# G778A.net
KiCad netlist of a schematic drawn in EAGLE
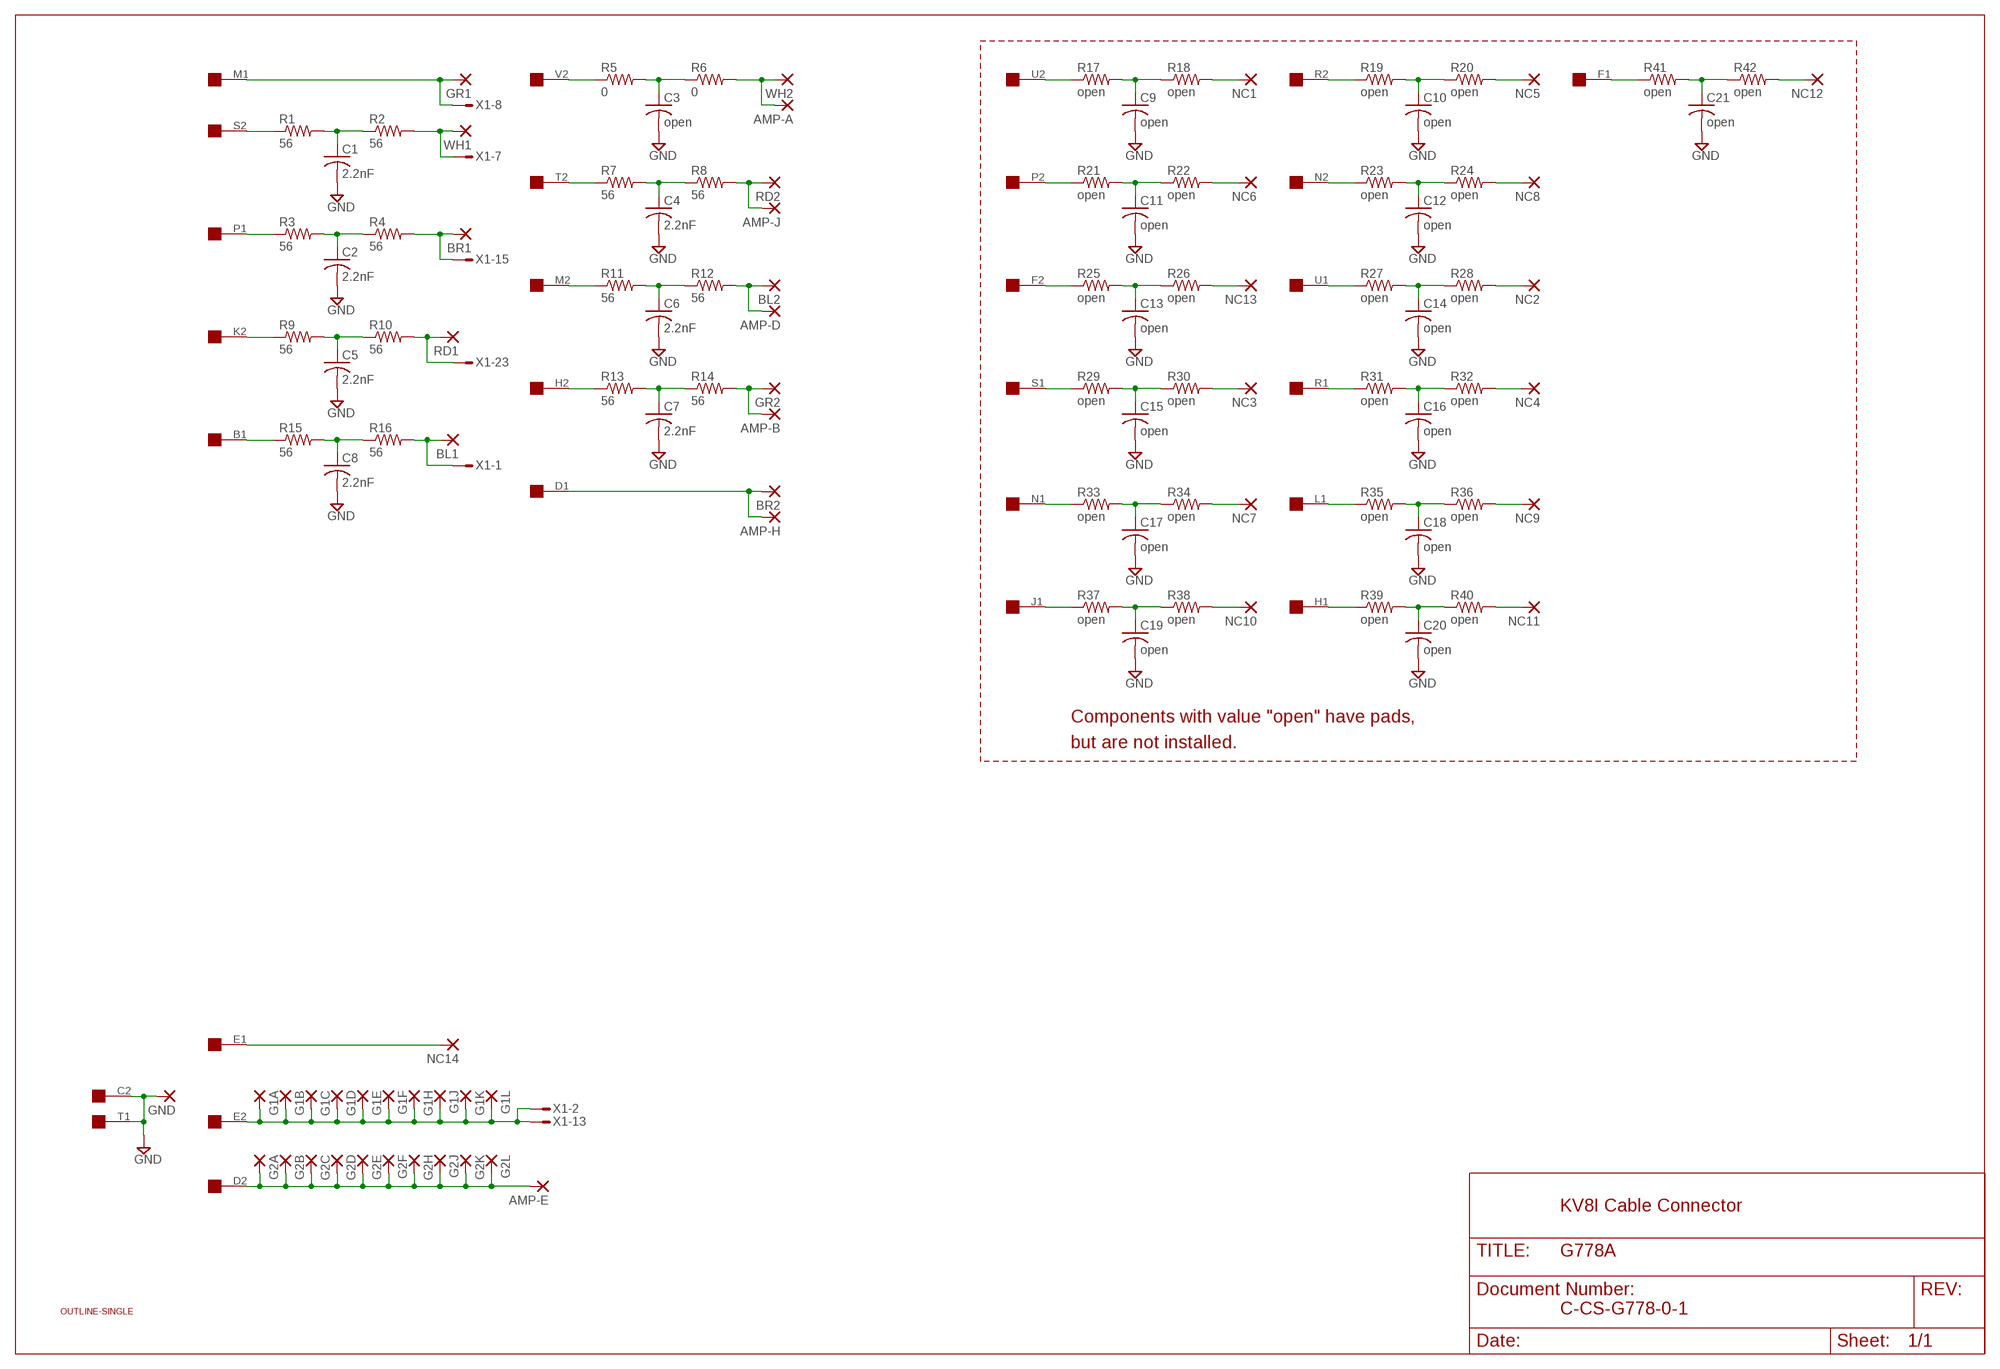
[diagram p0: schematic, sheet 1]

(export (version "E")
  (design (tool "Eeschema 10.0.6"))
  (components
    (comp (ref "AMP-A")
      (value "2,54/1,0")
      (footprint "eagle-import:2,54_1,0")
      (libsource (lib "eagle-import") (part "2,54/1,0"))
    )
    (comp (ref "AMP-B")
      (value "2,54/1,0")
      (footprint "eagle-import:2,54_1,0")
      (libsource (lib "eagle-import") (part "2,54/1,0"))
    )
    (comp (ref "AMP-D")
      (value "2,54/1,0")
      (footprint "eagle-import:2,54_1,0")
      (libsource (lib "eagle-import") (part "2,54/1,0"))
    )
    (comp (ref "AMP-E")
      (value "2,54/1,0")
      (footprint "eagle-import:2,54_1,0")
      (libsource (lib "eagle-import") (part "2,54/1,0"))
    )
    (comp (ref "AMP-H")
      (value "2,54/1,0")
      (footprint "eagle-import:2,54_1,0")
      (libsource (lib "eagle-import") (part "2,54/1,0"))
    )
    (comp (ref "AMP-J")
      (value "2,54/1,0")
      (footprint "eagle-import:2,54_1,0")
      (libsource (lib "eagle-import") (part "2,54/1,0"))
    )
    (comp (ref "BL1")
      (value "2,54/1,0")
      (footprint "eagle-import:2,54_1,0")
      (libsource (lib "eagle-import") (part "2,54/1,0"))
    )
    (comp (ref "BL2")
      (value "2,54/1,0")
      (footprint "eagle-import:2,54_1,0")
      (libsource (lib "eagle-import") (part "2,54/1,0"))
    )
    (comp (ref "BR1")
      (value "2,54/1,0")
      (footprint "eagle-import:2,54_1,0")
      (libsource (lib "eagle-import") (part "2,54/1,0"))
    )
    (comp (ref "BR2")
      (value "2,54/1,0")
      (footprint "eagle-import:2,54_1,0")
      (libsource (lib "eagle-import") (part "2,54/1,0"))
    )
    (comp (ref "C1")
      (value "2.2nF")
      (footprint "eagle-import:C102-043X133")
      (libsource (lib "eagle-import") (part "C-US102-043X133"))
    )
    (comp (ref "C2")
      (value "2.2nF")
      (footprint "eagle-import:C102-043X133")
      (libsource (lib "eagle-import") (part "C-US102-043X133"))
    )
    (comp (ref "C3")
      (value "open")
      (footprint "eagle-import:C102-043X133")
      (libsource (lib "eagle-import") (part "C-US102-043X133"))
    )
    (comp (ref "C4")
      (value "2.2nF")
      (footprint "eagle-import:C102-043X133")
      (libsource (lib "eagle-import") (part "C-US102-043X133"))
    )
    (comp (ref "C5")
      (value "2.2nF")
      (footprint "eagle-import:C102-043X133")
      (libsource (lib "eagle-import") (part "C-US102-043X133"))
    )
    (comp (ref "C6")
      (value "2.2nF")
      (footprint "eagle-import:C102-043X133")
      (libsource (lib "eagle-import") (part "C-US102-043X133"))
    )
    (comp (ref "C7")
      (value "2.2nF")
      (footprint "eagle-import:C102-043X133")
      (libsource (lib "eagle-import") (part "C-US102-043X133"))
    )
    (comp (ref "C8")
      (value "2.2nF")
      (footprint "eagle-import:C102-043X133")
      (libsource (lib "eagle-import") (part "C-US102-043X133"))
    )
    (comp (ref "C9")
      (value "open")
      (footprint "eagle-import:C102-043X133")
      (libsource (lib "eagle-import") (part "C-US102-043X133"))
    )
    (comp (ref "C10")
      (value "open")
      (footprint "eagle-import:C102-043X133")
      (libsource (lib "eagle-import") (part "C-US102-043X133"))
    )
    (comp (ref "C11")
      (value "open")
      (footprint "eagle-import:C102-043X133")
      (libsource (lib "eagle-import") (part "C-US102-043X133"))
    )
    (comp (ref "C12")
      (value "open")
      (footprint "eagle-import:C102-043X133")
      (libsource (lib "eagle-import") (part "C-US102-043X133"))
    )
    (comp (ref "C13")
      (value "open")
      (footprint "eagle-import:C102-043X133")
      (libsource (lib "eagle-import") (part "C-US102-043X133"))
    )
    (comp (ref "C14")
      (value "open")
      (footprint "eagle-import:C102-043X133")
      (libsource (lib "eagle-import") (part "C-US102-043X133"))
    )
    (comp (ref "C15")
      (value "open")
      (footprint "eagle-import:C102-043X133")
      (libsource (lib "eagle-import") (part "C-US102-043X133"))
    )
    (comp (ref "C16")
      (value "open")
      (footprint "eagle-import:C102-043X133")
      (libsource (lib "eagle-import") (part "C-US102-043X133"))
    )
    (comp (ref "C17")
      (value "open")
      (footprint "eagle-import:C102-043X133")
      (libsource (lib "eagle-import") (part "C-US102-043X133"))
    )
    (comp (ref "C18")
      (value "open")
      (footprint "eagle-import:C102-043X133")
      (libsource (lib "eagle-import") (part "C-US102-043X133"))
    )
    (comp (ref "C19")
      (value "open")
      (footprint "eagle-import:C102-043X133")
      (libsource (lib "eagle-import") (part "C-US102-043X133"))
    )
    (comp (ref "C20")
      (value "open")
      (footprint "eagle-import:C102-043X133")
      (libsource (lib "eagle-import") (part "C-US102-043X133"))
    )
    (comp (ref "C21")
      (value "open")
      (footprint "eagle-import:C102-043X133")
      (libsource (lib "eagle-import") (part "C-US102-043X133"))
    )
    (comp (ref "G1A")
      (value "2,54/1,0")
      (footprint "eagle-import:2,54_1,0")
      (libsource (lib "eagle-import") (part "2,54/1,0"))
    )
    (comp (ref "G1B")
      (value "2,54/1,0")
      (footprint "eagle-import:2,54_1,0")
      (libsource (lib "eagle-import") (part "2,54/1,0"))
    )
    (comp (ref "G1C")
      (value "2,54/1,0")
      (footprint "eagle-import:2,54_1,0")
      (libsource (lib "eagle-import") (part "2,54/1,0"))
    )
    (comp (ref "G1D")
      (value "2,54/1,0")
      (footprint "eagle-import:2,54_1,0")
      (libsource (lib "eagle-import") (part "2,54/1,0"))
    )
    (comp (ref "G1E")
      (value "2,54/1,0")
      (footprint "eagle-import:2,54_1,0")
      (libsource (lib "eagle-import") (part "2,54/1,0"))
    )
    (comp (ref "G1F")
      (value "2,54/1,0")
      (footprint "eagle-import:2,54_1,0")
      (libsource (lib "eagle-import") (part "2,54/1,0"))
    )
    (comp (ref "G1H")
      (value "2,54/1,0")
      (footprint "eagle-import:2,54_1,0")
      (libsource (lib "eagle-import") (part "2,54/1,0"))
    )
    (comp (ref "G1J")
      (value "2,54/1,0")
      (footprint "eagle-import:2,54_1,0")
      (libsource (lib "eagle-import") (part "2,54/1,0"))
    )
    (comp (ref "G1K")
      (value "2,54/1,0")
      (footprint "eagle-import:2,54_1,0")
      (libsource (lib "eagle-import") (part "2,54/1,0"))
    )
    (comp (ref "G1L")
      (value "2,54/1,0")
      (footprint "eagle-import:2,54_1,0")
      (libsource (lib "eagle-import") (part "2,54/1,0"))
    )
    (comp (ref "G2A")
      (value "2,54/1,0")
      (footprint "eagle-import:2,54_1,0")
      (libsource (lib "eagle-import") (part "2,54/1,0"))
    )
    (comp (ref "G2B")
      (value "2,54/1,0")
      (footprint "eagle-import:2,54_1,0")
      (libsource (lib "eagle-import") (part "2,54/1,0"))
    )
    (comp (ref "G2C")
      (value "2,54/1,0")
      (footprint "eagle-import:2,54_1,0")
      (libsource (lib "eagle-import") (part "2,54/1,0"))
    )
    (comp (ref "G2D")
      (value "2,54/1,0")
      (footprint "eagle-import:2,54_1,0")
      (libsource (lib "eagle-import") (part "2,54/1,0"))
    )
    (comp (ref "G2E")
      (value "2,54/1,0")
      (footprint "eagle-import:2,54_1,0")
      (libsource (lib "eagle-import") (part "2,54/1,0"))
    )
    (comp (ref "G2F")
      (value "2,54/1,0")
      (footprint "eagle-import:2,54_1,0")
      (libsource (lib "eagle-import") (part "2,54/1,0"))
    )
    (comp (ref "G2H")
      (value "2,54/1,0")
      (footprint "eagle-import:2,54_1,0")
      (libsource (lib "eagle-import") (part "2,54/1,0"))
    )
    (comp (ref "G2J")
      (value "2,54/1,0")
      (footprint "eagle-import:2,54_1,0")
      (libsource (lib "eagle-import") (part "2,54/1,0"))
    )
    (comp (ref "G2K")
      (value "2,54/1,0")
      (footprint "eagle-import:2,54_1,0")
      (libsource (lib "eagle-import") (part "2,54/1,0"))
    )
    (comp (ref "G2L")
      (value "2,54/1,0")
      (footprint "eagle-import:2,54_1,0")
      (libsource (lib "eagle-import") (part "2,54/1,0"))
    )
    (comp (ref "GND")
      (value "2,54/1,0")
      (footprint "eagle-import:2,54_1,0")
      (libsource (lib "eagle-import") (part "2,54/1,0"))
    )
    (comp (ref "GR1")
      (value "2,54/1,0")
      (footprint "eagle-import:2,54_1,0")
      (libsource (lib "eagle-import") (part "2,54/1,0"))
    )
    (comp (ref "GR2")
      (value "2,54/1,0")
      (footprint "eagle-import:2,54_1,0")
      (libsource (lib "eagle-import") (part "2,54/1,0"))
    )
    (comp (ref "NC1")
      (value "2,54/1,0")
      (footprint "eagle-import:2,54_1,0")
      (libsource (lib "eagle-import") (part "2,54/1,0"))
    )
    (comp (ref "NC2")
      (value "2,54/1,0")
      (footprint "eagle-import:2,54_1,0")
      (libsource (lib "eagle-import") (part "2,54/1,0"))
    )
    (comp (ref "NC3")
      (value "2,54/1,0")
      (footprint "eagle-import:2,54_1,0")
      (libsource (lib "eagle-import") (part "2,54/1,0"))
    )
    (comp (ref "NC4")
      (value "2,54/1,0")
      (footprint "eagle-import:2,54_1,0")
      (libsource (lib "eagle-import") (part "2,54/1,0"))
    )
    (comp (ref "NC5")
      (value "2,54/1,0")
      (footprint "eagle-import:2,54_1,0")
      (libsource (lib "eagle-import") (part "2,54/1,0"))
    )
    (comp (ref "NC6")
      (value "2,54/1,0")
      (footprint "eagle-import:2,54_1,0")
      (libsource (lib "eagle-import") (part "2,54/1,0"))
    )
    (comp (ref "NC7")
      (value "2,54/1,0")
      (footprint "eagle-import:2,54_1,0")
      (libsource (lib "eagle-import") (part "2,54/1,0"))
    )
    (comp (ref "NC8")
      (value "2,54/1,0")
      (footprint "eagle-import:2,54_1,0")
      (libsource (lib "eagle-import") (part "2,54/1,0"))
    )
    (comp (ref "NC9")
      (value "2,54/1,0")
      (footprint "eagle-import:2,54_1,0")
      (libsource (lib "eagle-import") (part "2,54/1,0"))
    )
    (comp (ref "NC10")
      (value "2,54/1,0")
      (footprint "eagle-import:2,54_1,0")
      (libsource (lib "eagle-import") (part "2,54/1,0"))
    )
    (comp (ref "NC11")
      (value "2,54/1,0")
      (footprint "eagle-import:2,54_1,0")
      (libsource (lib "eagle-import") (part "2,54/1,0"))
    )
    (comp (ref "NC12")
      (value "2,54/1,0")
      (footprint "eagle-import:2,54_1,0")
      (libsource (lib "eagle-import") (part "2,54/1,0"))
    )
    (comp (ref "NC13")
      (value "2,54/1,0")
      (footprint "eagle-import:2,54_1,0")
      (libsource (lib "eagle-import") (part "2,54/1,0"))
    )
    (comp (ref "NC14")
      (value "2,54/1,0")
      (footprint "eagle-import:2,54_1,0")
      (libsource (lib "eagle-import") (part "2,54/1,0"))
    )
    (comp (ref "R1")
      (value "56")
      (footprint "eagle-import:0207_10")
      (libsource (lib "eagle-import") (part "R-US_0207/10"))
    )
    (comp (ref "R2")
      (value "56")
      (footprint "eagle-import:0207_10")
      (libsource (lib "eagle-import") (part "R-US_0207/10"))
    )
    (comp (ref "R3")
      (value "56")
      (footprint "eagle-import:0207_10")
      (libsource (lib "eagle-import") (part "R-US_0207/10"))
    )
    (comp (ref "R4")
      (value "56")
      (footprint "eagle-import:0207_10")
      (libsource (lib "eagle-import") (part "R-US_0207/10"))
    )
    (comp (ref "R5")
      (value "0")
      (footprint "eagle-import:0207_10")
      (libsource (lib "eagle-import") (part "R-US_0207/10"))
    )
    (comp (ref "R6")
      (value "0")
      (footprint "eagle-import:0207_10")
      (libsource (lib "eagle-import") (part "R-US_0207/10"))
    )
    (comp (ref "R7")
      (value "56")
      (footprint "eagle-import:0207_10")
      (libsource (lib "eagle-import") (part "R-US_0207/10"))
    )
    (comp (ref "R8")
      (value "56")
      (footprint "eagle-import:0207_10")
      (libsource (lib "eagle-import") (part "R-US_0207/10"))
    )
    (comp (ref "R9")
      (value "56")
      (footprint "eagle-import:0207_10")
      (libsource (lib "eagle-import") (part "R-US_0207/10"))
    )
    (comp (ref "R10")
      (value "56")
      (footprint "eagle-import:0207_10")
      (libsource (lib "eagle-import") (part "R-US_0207/10"))
    )
    (comp (ref "R11")
      (value "56")
      (footprint "eagle-import:0207_10")
      (libsource (lib "eagle-import") (part "R-US_0207/10"))
    )
    (comp (ref "R12")
      (value "56")
      (footprint "eagle-import:0207_10")
      (libsource (lib "eagle-import") (part "R-US_0207/10"))
    )
    (comp (ref "R13")
      (value "56")
      (footprint "eagle-import:0207_10")
      (libsource (lib "eagle-import") (part "R-US_0207/10"))
    )
    (comp (ref "R14")
      (value "56")
      (footprint "eagle-import:0207_10")
      (libsource (lib "eagle-import") (part "R-US_0207/10"))
    )
    (comp (ref "R15")
      (value "56")
      (footprint "eagle-import:0207_10")
      (libsource (lib "eagle-import") (part "R-US_0207/10"))
    )
    (comp (ref "R16")
      (value "56")
      (footprint "eagle-import:0207_10")
      (libsource (lib "eagle-import") (part "R-US_0207/10"))
    )
    (comp (ref "R17")
      (value "open")
      (footprint "eagle-import:0207_10")
      (libsource (lib "eagle-import") (part "R-US_0207/10"))
    )
    (comp (ref "R18")
      (value "open")
      (footprint "eagle-import:0207_10")
      (libsource (lib "eagle-import") (part "R-US_0207/10"))
    )
    (comp (ref "R19")
      (value "open")
      (footprint "eagle-import:0207_10")
      (libsource (lib "eagle-import") (part "R-US_0207/10"))
    )
    (comp (ref "R20")
      (value "open")
      (footprint "eagle-import:0207_10")
      (libsource (lib "eagle-import") (part "R-US_0207/10"))
    )
    (comp (ref "R21")
      (value "open")
      (footprint "eagle-import:0207_10")
      (libsource (lib "eagle-import") (part "R-US_0207/10"))
    )
    (comp (ref "R22")
      (value "open")
      (footprint "eagle-import:0207_10")
      (libsource (lib "eagle-import") (part "R-US_0207/10"))
    )
    (comp (ref "R23")
      (value "open")
      (footprint "eagle-import:0207_10")
      (libsource (lib "eagle-import") (part "R-US_0207/10"))
    )
    (comp (ref "R24")
      (value "open")
      (footprint "eagle-import:0207_10")
      (libsource (lib "eagle-import") (part "R-US_0207/10"))
    )
    (comp (ref "R25")
      (value "open")
      (footprint "eagle-import:0207_10")
      (libsource (lib "eagle-import") (part "R-US_0207/10"))
    )
    (comp (ref "R26")
      (value "open")
      (footprint "eagle-import:0207_10")
      (libsource (lib "eagle-import") (part "R-US_0207/10"))
    )
    (comp (ref "R27")
      (value "open")
      (footprint "eagle-import:0207_10")
      (libsource (lib "eagle-import") (part "R-US_0207/10"))
    )
    (comp (ref "R28")
      (value "open")
      (footprint "eagle-import:0207_10")
      (libsource (lib "eagle-import") (part "R-US_0207/10"))
    )
    (comp (ref "R29")
      (value "open")
      (footprint "eagle-import:0207_10")
      (libsource (lib "eagle-import") (part "R-US_0207/10"))
    )
    (comp (ref "R30")
      (value "open")
      (footprint "eagle-import:0207_10")
      (libsource (lib "eagle-import") (part "R-US_0207/10"))
    )
    (comp (ref "R31")
      (value "open")
      (footprint "eagle-import:0207_10")
      (libsource (lib "eagle-import") (part "R-US_0207/10"))
    )
    (comp (ref "R32")
      (value "open")
      (footprint "eagle-import:0207_10")
      (libsource (lib "eagle-import") (part "R-US_0207/10"))
    )
    (comp (ref "R33")
      (value "open")
      (footprint "eagle-import:0207_10")
      (libsource (lib "eagle-import") (part "R-US_0207/10"))
    )
    (comp (ref "R34")
      (value "open")
      (footprint "eagle-import:0207_10")
      (libsource (lib "eagle-import") (part "R-US_0207/10"))
    )
    (comp (ref "R35")
      (value "open")
      (footprint "eagle-import:0207_10")
      (libsource (lib "eagle-import") (part "R-US_0207/10"))
    )
    (comp (ref "R36")
      (value "open")
      (footprint "eagle-import:0207_10")
      (libsource (lib "eagle-import") (part "R-US_0207/10"))
    )
    (comp (ref "R37")
      (value "open")
      (footprint "eagle-import:0207_10")
      (libsource (lib "eagle-import") (part "R-US_0207/10"))
    )
    (comp (ref "R38")
      (value "open")
      (footprint "eagle-import:0207_10")
      (libsource (lib "eagle-import") (part "R-US_0207/10"))
    )
    (comp (ref "R39")
      (value "open")
      (footprint "eagle-import:0207_10")
      (libsource (lib "eagle-import") (part "R-US_0207/10"))
    )
    (comp (ref "R40")
      (value "open")
      (footprint "eagle-import:0207_10")
      (libsource (lib "eagle-import") (part "R-US_0207/10"))
    )
    (comp (ref "R41")
      (value "open")
      (footprint "eagle-import:0207_10")
      (libsource (lib "eagle-import") (part "R-US_0207/10"))
    )
    (comp (ref "R42")
      (value "open")
      (footprint "eagle-import:0207_10")
      (libsource (lib "eagle-import") (part "R-US_0207/10"))
    )
    (comp (ref "RD1")
      (value "2,54/1,0")
      (footprint "eagle-import:2,54_1,0")
      (libsource (lib "eagle-import") (part "2,54/1,0"))
    )
    (comp (ref "RD2")
      (value "2,54/1,0")
      (footprint "eagle-import:2,54_1,0")
      (libsource (lib "eagle-import") (part "2,54/1,0"))
    )
    (comp (ref "U$1")
      (value "SINGLE")
      (footprint "eagle-import:EDGE-CON2")
      (libsource (lib "eagle-import") (part "SINGLE"))
    )
    (comp (ref "U$2")
      (value "OUTLINE-SINGLE")
      (footprint "eagle-import:SINGLE")
      (libsource (lib "eagle-import") (part "OUTLINE-SINGLE"))
    )
    (comp (ref "WH1")
      (value "2,54/1,0")
      (footprint "eagle-import:2,54_1,0")
      (libsource (lib "eagle-import") (part "2,54/1,0"))
    )
    (comp (ref "WH2")
      (value "2,54/1,0")
      (footprint "eagle-import:2,54_1,0")
      (libsource (lib "eagle-import") (part "2,54/1,0"))
    )
    (comp (ref "X1")
      (value "M25VS")
      (footprint "eagle-import:M25V")
      (libsource (lib "eagle-import") (part "M25?SV"))
    )
  )
  (nets
    (net (code "1") (name "GND") (class "Default")
      (node (ref "C1") (pin "2") (pinfunction "2_2") (pintype "passive"))
      (node (ref "C10") (pin "2") (pinfunction "2_2") (pintype "passive"))
      (node (ref "C11") (pin "2") (pinfunction "2_2") (pintype "passive"))
      (node (ref "C12") (pin "2") (pinfunction "2_2") (pintype "passive"))
      (node (ref "C13") (pin "2") (pinfunction "2_2") (pintype "passive"))
      (node (ref "C14") (pin "2") (pinfunction "2_2") (pintype "passive"))
      (node (ref "C15") (pin "2") (pinfunction "2_2") (pintype "passive"))
      (node (ref "C16") (pin "2") (pinfunction "2_2") (pintype "passive"))
      (node (ref "C17") (pin "2") (pinfunction "2_2") (pintype "passive"))
      (node (ref "C18") (pin "2") (pinfunction "2_2") (pintype "passive"))
      (node (ref "C19") (pin "2") (pinfunction "2_2") (pintype "passive"))
      (node (ref "C2") (pin "2") (pinfunction "2_2") (pintype "passive"))
      (node (ref "C20") (pin "2") (pinfunction "2_2") (pintype "passive"))
      (node (ref "C21") (pin "2") (pinfunction "2_2") (pintype "passive"))
      (node (ref "C3") (pin "2") (pinfunction "2_2") (pintype "passive"))
      (node (ref "C4") (pin "2") (pinfunction "2_2") (pintype "passive"))
      (node (ref "C5") (pin "2") (pinfunction "2_2") (pintype "passive"))
      (node (ref "C6") (pin "2") (pinfunction "2_2") (pintype "passive"))
      (node (ref "C7") (pin "2") (pinfunction "2_2") (pintype "passive"))
      (node (ref "C8") (pin "2") (pinfunction "2_2") (pintype "passive"))
      (node (ref "C9") (pin "2") (pinfunction "2_2") (pintype "passive"))
      (node (ref "GND") (pin "1") (pinfunction "P_1") (pintype "passive"))
      (node (ref "U$1") (pin "C2") (pinfunction "1_C2") (pintype "bidirectional"))
      (node (ref "U$1") (pin "T1") (pinfunction "1_T1") (pintype "bidirectional"))
    )
    (net (code "2") (name "Net-(AMP-A-P)") (class "Default")
      (node (ref "AMP-A") (pin "1") (pinfunction "P_1") (pintype "passive"))
      (node (ref "R6") (pin "2") (pinfunction "2_2") (pintype "passive"))
      (node (ref "WH2") (pin "1") (pinfunction "P_1") (pintype "passive"))
    )
    (net (code "3") (name "Net-(AMP-B-P)") (class "Default")
      (node (ref "AMP-B") (pin "1") (pinfunction "P_1") (pintype "passive"))
      (node (ref "GR2") (pin "1") (pinfunction "P_1") (pintype "passive"))
      (node (ref "R14") (pin "2") (pinfunction "2_2") (pintype "passive"))
    )
    (net (code "4") (name "Net-(AMP-D-P)") (class "Default")
      (node (ref "AMP-D") (pin "1") (pinfunction "P_1") (pintype "passive"))
      (node (ref "BL2") (pin "1") (pinfunction "P_1") (pintype "passive"))
      (node (ref "R12") (pin "2") (pinfunction "2_2") (pintype "passive"))
    )
    (net (code "5") (name "Net-(AMP-E-P)") (class "Default")
      (node (ref "AMP-E") (pin "1") (pinfunction "P_1") (pintype "passive"))
      (node (ref "G2A") (pin "1") (pinfunction "P_1") (pintype "passive"))
      (node (ref "G2B") (pin "1") (pinfunction "P_1") (pintype "passive"))
      (node (ref "G2C") (pin "1") (pinfunction "P_1") (pintype "passive"))
      (node (ref "G2D") (pin "1") (pinfunction "P_1") (pintype "passive"))
      (node (ref "G2E") (pin "1") (pinfunction "P_1") (pintype "passive"))
      (node (ref "G2F") (pin "1") (pinfunction "P_1") (pintype "passive"))
      (node (ref "G2H") (pin "1") (pinfunction "P_1") (pintype "passive"))
      (node (ref "G2J") (pin "1") (pinfunction "P_1") (pintype "passive"))
      (node (ref "G2K") (pin "1") (pinfunction "P_1") (pintype "passive"))
      (node (ref "G2L") (pin "1") (pinfunction "P_1") (pintype "passive"))
      (node (ref "U$1") (pin "D2") (pinfunction "1_D2") (pintype "bidirectional"))
    )
    (net (code "6") (name "Net-(AMP-H-P)") (class "Default")
      (node (ref "AMP-H") (pin "1") (pinfunction "P_1") (pintype "passive"))
      (node (ref "BR2") (pin "1") (pinfunction "P_1") (pintype "passive"))
      (node (ref "U$1") (pin "D1") (pinfunction "1_D1") (pintype "bidirectional"))
    )
    (net (code "7") (name "Net-(AMP-J-P)") (class "Default")
      (node (ref "AMP-J") (pin "1") (pinfunction "P_1") (pintype "passive"))
      (node (ref "R8") (pin "2") (pinfunction "2_2") (pintype "passive"))
      (node (ref "RD2") (pin "1") (pinfunction "P_1") (pintype "passive"))
    )
    (net (code "8") (name "Net-(BL1-P)") (class "Default")
      (node (ref "BL1") (pin "1") (pinfunction "P_1") (pintype "passive"))
      (node (ref "R16") (pin "2") (pinfunction "2_2") (pintype "passive"))
      (node (ref "X1") (pin "1") (pinfunction "M_1") (pintype "passive"))
    )
    (net (code "9") (name "Net-(BR1-P)") (class "Default")
      (node (ref "BR1") (pin "1") (pinfunction "P_1") (pintype "passive"))
      (node (ref "R4") (pin "2") (pinfunction "2_2") (pintype "passive"))
      (node (ref "X1") (pin "15") (pinfunction "M_15") (pintype "passive"))
    )
    (net (code "10") (name "Net-(C1-Pad1)") (class "Default")
      (node (ref "C1") (pin "1") (pinfunction "1_1") (pintype "passive"))
      (node (ref "R1") (pin "2") (pinfunction "2_2") (pintype "passive"))
      (node (ref "R2") (pin "1") (pinfunction "1_1") (pintype "passive"))
    )
    (net (code "11") (name "Net-(C2-Pad1)") (class "Default")
      (node (ref "C2") (pin "1") (pinfunction "1_1") (pintype "passive"))
      (node (ref "R3") (pin "2") (pinfunction "2_2") (pintype "passive"))
      (node (ref "R4") (pin "1") (pinfunction "1_1") (pintype "passive"))
    )
    (net (code "12") (name "Net-(C3-Pad1)") (class "Default")
      (node (ref "C3") (pin "1") (pinfunction "1_1") (pintype "passive"))
      (node (ref "R5") (pin "2") (pinfunction "2_2") (pintype "passive"))
      (node (ref "R6") (pin "1") (pinfunction "1_1") (pintype "passive"))
    )
    (net (code "13") (name "Net-(C4-Pad1)") (class "Default")
      (node (ref "C4") (pin "1") (pinfunction "1_1") (pintype "passive"))
      (node (ref "R7") (pin "2") (pinfunction "2_2") (pintype "passive"))
      (node (ref "R8") (pin "1") (pinfunction "1_1") (pintype "passive"))
    )
    (net (code "14") (name "Net-(C5-Pad1)") (class "Default")
      (node (ref "C5") (pin "1") (pinfunction "1_1") (pintype "passive"))
      (node (ref "R10") (pin "1") (pinfunction "1_1") (pintype "passive"))
      (node (ref "R9") (pin "2") (pinfunction "2_2") (pintype "passive"))
    )
    (net (code "15") (name "Net-(C6-Pad1)") (class "Default")
      (node (ref "C6") (pin "1") (pinfunction "1_1") (pintype "passive"))
      (node (ref "R11") (pin "2") (pinfunction "2_2") (pintype "passive"))
      (node (ref "R12") (pin "1") (pinfunction "1_1") (pintype "passive"))
    )
    (net (code "16") (name "Net-(C7-Pad1)") (class "Default")
      (node (ref "C7") (pin "1") (pinfunction "1_1") (pintype "passive"))
      (node (ref "R13") (pin "2") (pinfunction "2_2") (pintype "passive"))
      (node (ref "R14") (pin "1") (pinfunction "1_1") (pintype "passive"))
    )
    (net (code "17") (name "Net-(C8-Pad1)") (class "Default")
      (node (ref "C8") (pin "1") (pinfunction "1_1") (pintype "passive"))
      (node (ref "R15") (pin "2") (pinfunction "2_2") (pintype "passive"))
      (node (ref "R16") (pin "1") (pinfunction "1_1") (pintype "passive"))
    )
    (net (code "18") (name "Net-(C9-Pad1)") (class "Default")
      (node (ref "C9") (pin "1") (pinfunction "1_1") (pintype "passive"))
      (node (ref "R17") (pin "2") (pinfunction "2_2") (pintype "passive"))
      (node (ref "R18") (pin "1") (pinfunction "1_1") (pintype "passive"))
    )
    (net (code "19") (name "Net-(C10-Pad1)") (class "Default")
      (node (ref "C10") (pin "1") (pinfunction "1_1") (pintype "passive"))
      (node (ref "R19") (pin "2") (pinfunction "2_2") (pintype "passive"))
      (node (ref "R20") (pin "1") (pinfunction "1_1") (pintype "passive"))
    )
    (net (code "20") (name "Net-(C11-Pad1)") (class "Default")
      (node (ref "C11") (pin "1") (pinfunction "1_1") (pintype "passive"))
      (node (ref "R21") (pin "2") (pinfunction "2_2") (pintype "passive"))
      (node (ref "R22") (pin "1") (pinfunction "1_1") (pintype "passive"))
    )
    (net (code "21") (name "Net-(C12-Pad1)") (class "Default")
      (node (ref "C12") (pin "1") (pinfunction "1_1") (pintype "passive"))
      (node (ref "R23") (pin "2") (pinfunction "2_2") (pintype "passive"))
      (node (ref "R24") (pin "1") (pinfunction "1_1") (pintype "passive"))
    )
    (net (code "22") (name "Net-(C13-Pad1)") (class "Default")
      (node (ref "C13") (pin "1") (pinfunction "1_1") (pintype "passive"))
      (node (ref "R25") (pin "2") (pinfunction "2_2") (pintype "passive"))
      (node (ref "R26") (pin "1") (pinfunction "1_1") (pintype "passive"))
    )
    (net (code "23") (name "Net-(C14-Pad1)") (class "Default")
      (node (ref "C14") (pin "1") (pinfunction "1_1") (pintype "passive"))
      (node (ref "R27") (pin "2") (pinfunction "2_2") (pintype "passive"))
      (node (ref "R28") (pin "1") (pinfunction "1_1") (pintype "passive"))
    )
    (net (code "24") (name "Net-(C15-Pad1)") (class "Default")
      (node (ref "C15") (pin "1") (pinfunction "1_1") (pintype "passive"))
      (node (ref "R29") (pin "2") (pinfunction "2_2") (pintype "passive"))
      (node (ref "R30") (pin "1") (pinfunction "1_1") (pintype "passive"))
    )
    (net (code "25") (name "Net-(C16-Pad1)") (class "Default")
      (node (ref "C16") (pin "1") (pinfunction "1_1") (pintype "passive"))
      (node (ref "R31") (pin "2") (pinfunction "2_2") (pintype "passive"))
      (node (ref "R32") (pin "1") (pinfunction "1_1") (pintype "passive"))
    )
    (net (code "26") (name "Net-(C17-Pad1)") (class "Default")
      (node (ref "C17") (pin "1") (pinfunction "1_1") (pintype "passive"))
      (node (ref "R33") (pin "2") (pinfunction "2_2") (pintype "passive"))
      (node (ref "R34") (pin "1") (pinfunction "1_1") (pintype "passive"))
    )
    (net (code "27") (name "Net-(C18-Pad1)") (class "Default")
      (node (ref "C18") (pin "1") (pinfunction "1_1") (pintype "passive"))
      (node (ref "R35") (pin "2") (pinfunction "2_2") (pintype "passive"))
      (node (ref "R36") (pin "1") (pinfunction "1_1") (pintype "passive"))
    )
    (net (code "28") (name "Net-(C19-Pad1)") (class "Default")
      (node (ref "C19") (pin "1") (pinfunction "1_1") (pintype "passive"))
      (node (ref "R37") (pin "2") (pinfunction "2_2") (pintype "passive"))
      (node (ref "R38") (pin "1") (pinfunction "1_1") (pintype "passive"))
    )
    (net (code "29") (name "Net-(C20-Pad1)") (class "Default")
      (node (ref "C20") (pin "1") (pinfunction "1_1") (pintype "passive"))
      (node (ref "R39") (pin "2") (pinfunction "2_2") (pintype "passive"))
      (node (ref "R40") (pin "1") (pinfunction "1_1") (pintype "passive"))
    )
    (net (code "30") (name "Net-(C21-Pad1)") (class "Default")
      (node (ref "C21") (pin "1") (pinfunction "1_1") (pintype "passive"))
      (node (ref "R41") (pin "2") (pinfunction "2_2") (pintype "passive"))
      (node (ref "R42") (pin "1") (pinfunction "1_1") (pintype "passive"))
    )
    (net (code "31") (name "Net-(G1A-P)") (class "Default")
      (node (ref "G1A") (pin "1") (pinfunction "P_1") (pintype "passive"))
      (node (ref "G1B") (pin "1") (pinfunction "P_1") (pintype "passive"))
      (node (ref "G1C") (pin "1") (pinfunction "P_1") (pintype "passive"))
      (node (ref "G1D") (pin "1") (pinfunction "P_1") (pintype "passive"))
      (node (ref "G1E") (pin "1") (pinfunction "P_1") (pintype "passive"))
      (node (ref "G1F") (pin "1") (pinfunction "P_1") (pintype "passive"))
      (node (ref "G1H") (pin "1") (pinfunction "P_1") (pintype "passive"))
      (node (ref "G1J") (pin "1") (pinfunction "P_1") (pintype "passive"))
      (node (ref "G1K") (pin "1") (pinfunction "P_1") (pintype "passive"))
      (node (ref "G1L") (pin "1") (pinfunction "P_1") (pintype "passive"))
      (node (ref "U$1") (pin "E2") (pinfunction "1_E2") (pintype "bidirectional"))
      (node (ref "X1") (pin "13") (pinfunction "M_13") (pintype "passive"))
      (node (ref "X1") (pin "2") (pinfunction "M_2") (pintype "passive"))
    )
    (net (code "32") (name "Net-(GR1-P)") (class "Default")
      (node (ref "GR1") (pin "1") (pinfunction "P_1") (pintype "passive"))
      (node (ref "U$1") (pin "M1") (pinfunction "1_M1") (pintype "bidirectional"))
      (node (ref "X1") (pin "8") (pinfunction "M_8") (pintype "passive"))
    )
    (net (code "33") (name "Net-(NC1-P)") (class "Default")
      (node (ref "NC1") (pin "1") (pinfunction "P_1") (pintype "passive"))
      (node (ref "R18") (pin "2") (pinfunction "2_2") (pintype "passive"))
    )
    (net (code "34") (name "Net-(NC2-P)") (class "Default")
      (node (ref "NC2") (pin "1") (pinfunction "P_1") (pintype "passive"))
      (node (ref "R28") (pin "2") (pinfunction "2_2") (pintype "passive"))
    )
    (net (code "35") (name "Net-(NC3-P)") (class "Default")
      (node (ref "NC3") (pin "1") (pinfunction "P_1") (pintype "passive"))
      (node (ref "R30") (pin "2") (pinfunction "2_2") (pintype "passive"))
    )
    (net (code "36") (name "Net-(NC4-P)") (class "Default")
      (node (ref "NC4") (pin "1") (pinfunction "P_1") (pintype "passive"))
      (node (ref "R32") (pin "2") (pinfunction "2_2") (pintype "passive"))
    )
    (net (code "37") (name "Net-(NC5-P)") (class "Default")
      (node (ref "NC5") (pin "1") (pinfunction "P_1") (pintype "passive"))
      (node (ref "R20") (pin "2") (pinfunction "2_2") (pintype "passive"))
    )
    (net (code "38") (name "Net-(NC6-P)") (class "Default")
      (node (ref "NC6") (pin "1") (pinfunction "P_1") (pintype "passive"))
      (node (ref "R22") (pin "2") (pinfunction "2_2") (pintype "passive"))
    )
    (net (code "39") (name "Net-(NC7-P)") (class "Default")
      (node (ref "NC7") (pin "1") (pinfunction "P_1") (pintype "passive"))
      (node (ref "R34") (pin "2") (pinfunction "2_2") (pintype "passive"))
    )
    (net (code "40") (name "Net-(NC8-P)") (class "Default")
      (node (ref "NC8") (pin "1") (pinfunction "P_1") (pintype "passive"))
      (node (ref "R24") (pin "2") (pinfunction "2_2") (pintype "passive"))
    )
    (net (code "41") (name "Net-(NC9-P)") (class "Default")
      (node (ref "NC9") (pin "1") (pinfunction "P_1") (pintype "passive"))
      (node (ref "R36") (pin "2") (pinfunction "2_2") (pintype "passive"))
    )
    (net (code "42") (name "Net-(NC10-P)") (class "Default")
      (node (ref "NC10") (pin "1") (pinfunction "P_1") (pintype "passive"))
      (node (ref "R38") (pin "2") (pinfunction "2_2") (pintype "passive"))
    )
    (net (code "43") (name "Net-(NC11-P)") (class "Default")
      (node (ref "NC11") (pin "1") (pinfunction "P_1") (pintype "passive"))
      (node (ref "R40") (pin "2") (pinfunction "2_2") (pintype "passive"))
    )
    (net (code "44") (name "Net-(NC12-P)") (class "Default")
      (node (ref "NC12") (pin "1") (pinfunction "P_1") (pintype "passive"))
      (node (ref "R42") (pin "2") (pinfunction "2_2") (pintype "passive"))
    )
    (net (code "45") (name "Net-(NC13-P)") (class "Default")
      (node (ref "NC13") (pin "1") (pinfunction "P_1") (pintype "passive"))
      (node (ref "R26") (pin "2") (pinfunction "2_2") (pintype "passive"))
    )
    (net (code "46") (name "Net-(NC14-P)") (class "Default")
      (node (ref "NC14") (pin "1") (pinfunction "P_1") (pintype "passive"))
      (node (ref "U$1") (pin "E1") (pinfunction "1_E1") (pintype "bidirectional"))
    )
    (net (code "47") (name "Net-(RD1-P)") (class "Default")
      (node (ref "R10") (pin "2") (pinfunction "2_2") (pintype "passive"))
      (node (ref "RD1") (pin "1") (pinfunction "P_1") (pintype "passive"))
      (node (ref "X1") (pin "23") (pinfunction "M_23") (pintype "passive"))
    )
    (net (code "48") (name "Net-(U$1AA-1)") (class "Default")
      (node (ref "R31") (pin "1") (pinfunction "1_1") (pintype "passive"))
      (node (ref "U$1") (pin "R1") (pinfunction "1_R1") (pintype "bidirectional"))
    )
    (net (code "49") (name "Net-(U$1AB-1)") (class "Default")
      (node (ref "R19") (pin "1") (pinfunction "1_1") (pintype "passive"))
      (node (ref "U$1") (pin "R2") (pinfunction "1_R2") (pintype "bidirectional"))
    )
    (net (code "50") (name "Net-(U$1AC-1)") (class "Default")
      (node (ref "R29") (pin "1") (pinfunction "1_1") (pintype "passive"))
      (node (ref "U$1") (pin "S1") (pinfunction "1_S1") (pintype "bidirectional"))
    )
    (net (code "51") (name "Net-(U$1AD-1)") (class "Default")
      (node (ref "R1") (pin "1") (pinfunction "1_1") (pintype "passive"))
      (node (ref "U$1") (pin "S2") (pinfunction "1_S2") (pintype "bidirectional"))
    )
    (net (code "52") (name "Net-(U$1AF-1)") (class "Default")
      (node (ref "R7") (pin "1") (pinfunction "1_1") (pintype "passive"))
      (node (ref "U$1") (pin "T2") (pinfunction "1_T2") (pintype "bidirectional"))
    )
    (net (code "53") (name "Net-(U$1AG-1)") (class "Default")
      (node (ref "R27") (pin "1") (pinfunction "1_1") (pintype "passive"))
      (node (ref "U$1") (pin "U1") (pinfunction "1_U1") (pintype "bidirectional"))
    )
    (net (code "54") (name "Net-(U$1AH-1)") (class "Default")
      (node (ref "R17") (pin "1") (pinfunction "1_1") (pintype "passive"))
      (node (ref "U$1") (pin "U2") (pinfunction "1_U2") (pintype "bidirectional"))
    )
    (net (code "55") (name "Net-(U$1AJ-1)") (class "Default")
      (node (ref "R5") (pin "1") (pinfunction "1_1") (pintype "passive"))
      (node (ref "U$1") (pin "V2") (pinfunction "1_V2") (pintype "bidirectional"))
    )
    (net (code "56") (name "Net-(U$1C-1)") (class "Default")
      (node (ref "R15") (pin "1") (pinfunction "1_1") (pintype "passive"))
      (node (ref "U$1") (pin "B1") (pinfunction "1_B1") (pintype "bidirectional"))
    )
    (net (code "57") (name "Net-(U$1K-1)") (class "Default")
      (node (ref "R41") (pin "1") (pinfunction "1_1") (pintype "passive"))
      (node (ref "U$1") (pin "F1") (pinfunction "1_F1") (pintype "bidirectional"))
    )
    (net (code "58") (name "Net-(U$1L-1)") (class "Default")
      (node (ref "R25") (pin "1") (pinfunction "1_1") (pintype "passive"))
      (node (ref "U$1") (pin "F2") (pinfunction "1_F2") (pintype "bidirectional"))
    )
    (net (code "59") (name "Net-(U$1M-1)") (class "Default")
      (node (ref "R39") (pin "1") (pinfunction "1_1") (pintype "passive"))
      (node (ref "U$1") (pin "H1") (pinfunction "1_H1") (pintype "bidirectional"))
    )
    (net (code "60") (name "Net-(U$1N-1)") (class "Default")
      (node (ref "R13") (pin "1") (pinfunction "1_1") (pintype "passive"))
      (node (ref "U$1") (pin "H2") (pinfunction "1_H2") (pintype "bidirectional"))
    )
    (net (code "61") (name "Net-(U$1O-1)") (class "Default")
      (node (ref "R37") (pin "1") (pinfunction "1_1") (pintype "passive"))
      (node (ref "U$1") (pin "J1") (pinfunction "1_J1") (pintype "bidirectional"))
    )
    (net (code "62") (name "Net-(U$1R-1)") (class "Default")
      (node (ref "R9") (pin "1") (pinfunction "1_1") (pintype "passive"))
      (node (ref "U$1") (pin "K2") (pinfunction "1_K2") (pintype "bidirectional"))
    )
    (net (code "63") (name "Net-(U$1S-1)") (class "Default")
      (node (ref "R35") (pin "1") (pinfunction "1_1") (pintype "passive"))
      (node (ref "U$1") (pin "L1") (pinfunction "1_L1") (pintype "bidirectional"))
    )
    (net (code "64") (name "Net-(U$1V-1)") (class "Default")
      (node (ref "R11") (pin "1") (pinfunction "1_1") (pintype "passive"))
      (node (ref "U$1") (pin "M2") (pinfunction "1_M2") (pintype "bidirectional"))
    )
    (net (code "65") (name "Net-(U$1W-1)") (class "Default")
      (node (ref "R33") (pin "1") (pinfunction "1_1") (pintype "passive"))
      (node (ref "U$1") (pin "N1") (pinfunction "1_N1") (pintype "bidirectional"))
    )
    (net (code "66") (name "Net-(U$1X-1)") (class "Default")
      (node (ref "R23") (pin "1") (pinfunction "1_1") (pintype "passive"))
      (node (ref "U$1") (pin "N2") (pinfunction "1_N2") (pintype "bidirectional"))
    )
    (net (code "67") (name "Net-(U$1Y-1)") (class "Default")
      (node (ref "R3") (pin "1") (pinfunction "1_1") (pintype "passive"))
      (node (ref "U$1") (pin "P1") (pinfunction "1_P1") (pintype "bidirectional"))
    )
    (net (code "68") (name "Net-(U$1Z-1)") (class "Default")
      (node (ref "R21") (pin "1") (pinfunction "1_1") (pintype "passive"))
      (node (ref "U$1") (pin "P2") (pinfunction "1_P2") (pintype "bidirectional"))
    )
    (net (code "69") (name "Net-(WH1-P)") (class "Default")
      (node (ref "R2") (pin "2") (pinfunction "2_2") (pintype "passive"))
      (node (ref "WH1") (pin "1") (pinfunction "P_1") (pintype "passive"))
      (node (ref "X1") (pin "7") (pinfunction "M_7") (pintype "passive"))
    )
  )
)
